# MinipHV2_1.net
KiCad netlist of a schematic drawn in EAGLE
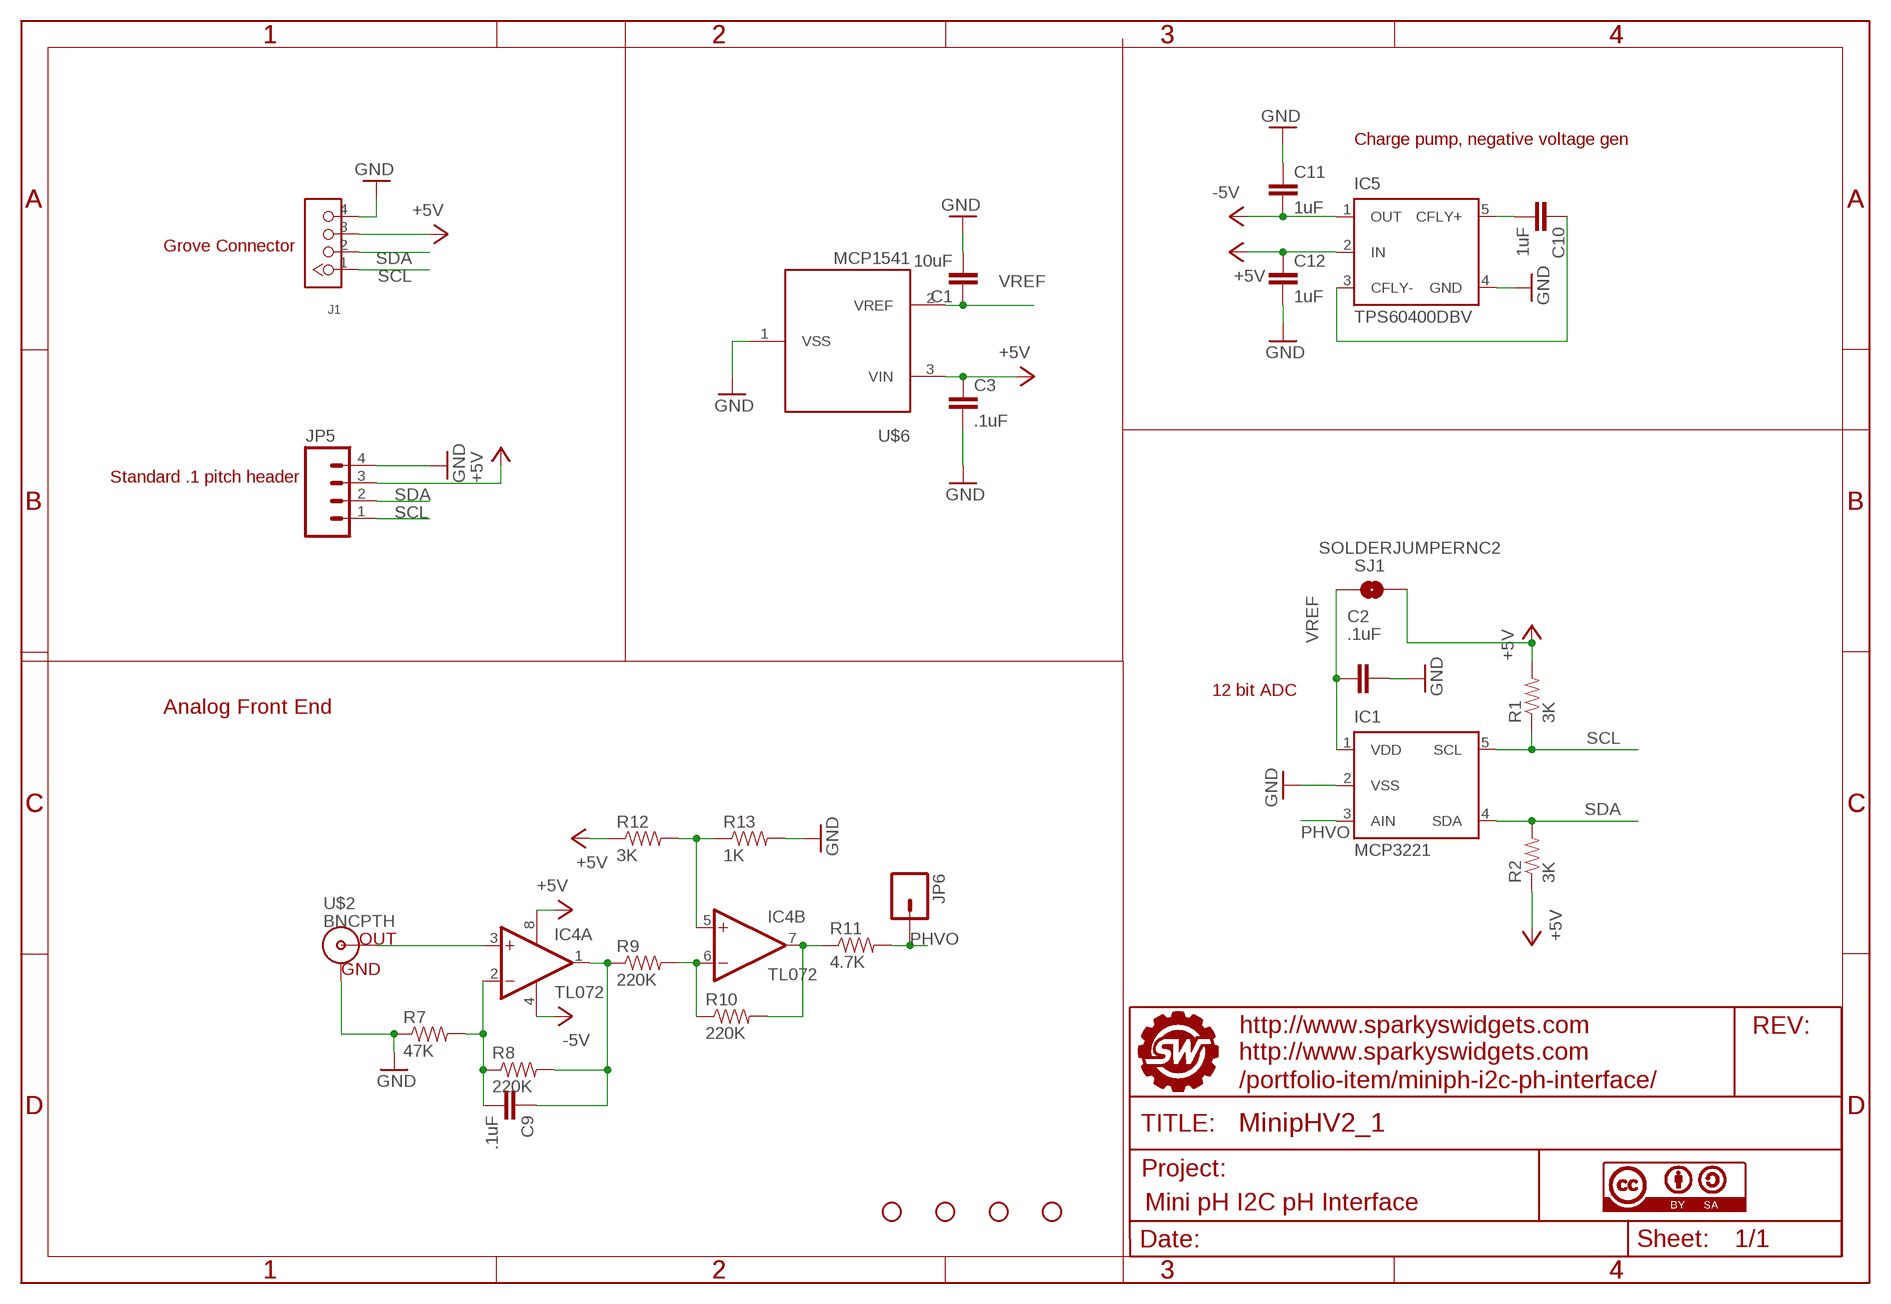
[diagram p0: schematic, sheet 1]

(export (version "E")
  (design (tool "Eeschema 10.0.6"))
  (components
    (comp (ref "C1")
      (value "10uF")
      (footprint "eagle-import:0805")
      (libsource (lib "eagle-import") (part "CAP0805"))
    )
    (comp (ref "C2")
      (value ".1uF")
      (footprint "eagle-import:0805")
      (libsource (lib "eagle-import") (part "CAP0805"))
    )
    (comp (ref "C3")
      (value ".1uF")
      (footprint "eagle-import:0805")
      (libsource (lib "eagle-import") (part "CAP0805"))
    )
    (comp (ref "C9")
      (value ".1uF")
      (footprint "eagle-import:0805")
      (libsource (lib "eagle-import") (part "CAP0805"))
    )
    (comp (ref "C10")
      (value "1uF")
      (footprint "eagle-import:0805")
      (libsource (lib "eagle-import") (part "CAP0805"))
    )
    (comp (ref "C11")
      (value "1uF")
      (footprint "eagle-import:0805")
      (libsource (lib "eagle-import") (part "CAP0805"))
    )
    (comp (ref "C12")
      (value "1uF")
      (footprint "eagle-import:0805")
      (libsource (lib "eagle-import") (part "CAP0805"))
    )
    (comp (ref "IC1")
      (value "MCP3221")
      (footprint "eagle-import:SOT23-DBV")
      (libsource (lib "eagle-import") (part "MCP3221"))
    )
    (comp (ref "IC4")
      (value "TL072")
      (footprint "eagle-import:SO08")
      (libsource (lib "eagle-import") (part "LM358D"))
    )
    (comp (ref "IC5")
      (value "TPS60400DBV")
      (footprint "eagle-import:SOT23-DBV")
      (libsource (lib "eagle-import") (part "TPS60400DBV"))
    )
    (comp (ref "J1")
      (value "TWIG-4P-2.0-2.0")
      (footprint "eagle-import:4P-2.0")
      (libsource (lib "eagle-import") (part "TWIG-4P-2.0-2.0"))
    )
    (comp (ref "JP1")
      (value "STAND-OFF")
      (footprint "eagle-import:STAND-OFF")
      (libsource (lib "eagle-import") (part "STAND-OFF"))
    )
    (comp (ref "JP2")
      (value "STAND-OFF")
      (footprint "eagle-import:STAND-OFF")
      (libsource (lib "eagle-import") (part "STAND-OFF"))
    )
    (comp (ref "JP3")
      (value "STAND-OFF")
      (footprint "eagle-import:STAND-OFF")
      (libsource (lib "eagle-import") (part "STAND-OFF"))
    )
    (comp (ref "JP4")
      (value "STAND-OFF")
      (footprint "eagle-import:STAND-OFF")
      (libsource (lib "eagle-import") (part "STAND-OFF"))
    )
    (comp (ref "JP5")
      (value "M04PTH")
      (footprint "eagle-import:1X04")
      (libsource (lib "eagle-import") (part "M04PTH"))
    )
    (comp (ref "JP6")
      (value "M01PTH_LONGPAD")
      (footprint "eagle-import:1X01_LONGPAD")
      (libsource (lib "eagle-import") (part "M01PTH_LONGPAD"))
    )
    (comp (ref "R1")
      (value "3K")
      (footprint "eagle-import:0805")
      (libsource (lib "eagle-import") (part "RESISTOR0805-RES"))
    )
    (comp (ref "R2")
      (value "3K")
      (footprint "eagle-import:0805")
      (libsource (lib "eagle-import") (part "RESISTOR0805-RES"))
    )
    (comp (ref "R7")
      (value "47K")
      (footprint "eagle-import:0805")
      (libsource (lib "eagle-import") (part "RESISTOR0805-RES"))
    )
    (comp (ref "R8")
      (value "220K")
      (footprint "eagle-import:0805")
      (libsource (lib "eagle-import") (part "RESISTOR0805-RES"))
    )
    (comp (ref "R9")
      (value "220K")
      (footprint "eagle-import:0805")
      (libsource (lib "eagle-import") (part "RESISTOR0805-RES"))
    )
    (comp (ref "R10")
      (value "220K")
      (footprint "eagle-import:0805")
      (libsource (lib "eagle-import") (part "RESISTOR0805-RES"))
    )
    (comp (ref "R11")
      (value "4.7K")
      (footprint "eagle-import:0805")
      (libsource (lib "eagle-import") (part "RESISTOR0805-RES"))
    )
    (comp (ref "R12")
      (value "3K")
      (footprint "eagle-import:0805")
      (libsource (lib "eagle-import") (part "RESISTOR0805-RES"))
    )
    (comp (ref "R13")
      (value "1K")
      (footprint "eagle-import:0805")
      (libsource (lib "eagle-import") (part "RESISTOR0805-RES"))
    )
    (comp (ref "SJ1")
      (value "SOLDERJUMPERNC2")
      (footprint "eagle-import:SJ_2S-NOTRACE")
      (libsource (lib "eagle-import") (part "SOLDERJUMPERNC2"))
    )
    (comp (ref "U$2")
      (value "BNCPTH")
      (footprint "eagle-import:BNC")
      (libsource (lib "eagle-import") (part "BNCPTH"))
    )
    (comp (ref "U$4")
      (value "FRAME_MINIPH")
      (footprint "eagle-import:SWPCBLOGOWITHINFO")
      (fields
        (field (name "PROJECT") "Mini pH I2C pH Interface")
        (field (name "URL1") "/portfolio-item/miniph-i2c-ph-interface/")
      )
      (libsource (lib "eagle-import") (part "FRAME_MINIPH"))
    )
    (comp (ref "U$5")
      (value "CC-BY-SA")
      (footprint "eagle-import:CC-BY-SA")
      (libsource (lib "eagle-import") (part "CC-BY-SA"))
    )
    (comp (ref "U$6")
      (value "MCP1541")
      (footprint "eagle-import:SOT-23")
      (libsource (lib "eagle-import") (part "MCP1541"))
    )
  )
  (nets
    (net (code "1") (name "+5V") (class "Default")
      (node (ref "C12") (pin "1") (pinfunction "1_1") (pintype "passive"))
      (node (ref "C3") (pin "1") (pinfunction "1_1") (pintype "passive"))
      (node (ref "IC4") (pin "8") (pinfunction "V+_8") (pintype "power_in"))
      (node (ref "IC5") (pin "2") (pinfunction "IN_2") (pintype "input"))
      (node (ref "J1") (pin "3") (pinfunction "3_3") (pintype "bidirectional"))
      (node (ref "JP5") (pin "3") (pinfunction "3_3") (pintype "passive"))
      (node (ref "R1") (pin "2") (pinfunction "2_2") (pintype "passive"))
      (node (ref "R12") (pin "1") (pinfunction "1_1") (pintype "passive"))
      (node (ref "R2") (pin "1") (pinfunction "1_1") (pintype "passive"))
      (node (ref "SJ1") (pin "2") (pinfunction "2_2") (pintype "passive"))
      (node (ref "U$6") (pin "3") (pinfunction "VIN_3") (pintype "power_in"))
    )
    (net (code "2") (name "-5V") (class "Default")
      (node (ref "C11") (pin "2") (pinfunction "2_2") (pintype "passive"))
      (node (ref "IC4") (pin "4") (pinfunction "V-_4") (pintype "power_in"))
      (node (ref "IC5") (pin "1") (pinfunction "OUT_1") (pintype "input"))
    )
    (net (code "3") (name "/PHVO") (class "Default")
      (node (ref "IC1") (pin "3") (pinfunction "AIN_3") (pintype "input"))
      (node (ref "JP6") (pin "1") (pinfunction "1_1") (pintype "passive"))
      (node (ref "R11") (pin "2") (pinfunction "2_2") (pintype "passive"))
    )
    (net (code "4") (name "/SCL") (class "Default")
      (node (ref "IC1") (pin "5") (pinfunction "SCL_5") (pintype "bidirectional"))
      (node (ref "J1") (pin "1") (pinfunction "1_1") (pintype "bidirectional"))
      (node (ref "JP5") (pin "1") (pinfunction "1_1") (pintype "passive"))
      (node (ref "R1") (pin "1") (pinfunction "1_1") (pintype "passive"))
    )
    (net (code "5") (name "/SDA") (class "Default")
      (node (ref "IC1") (pin "4") (pinfunction "SDA_4") (pintype "bidirectional"))
      (node (ref "J1") (pin "2") (pinfunction "2_2") (pintype "bidirectional"))
      (node (ref "JP5") (pin "2") (pinfunction "2_2") (pintype "passive"))
      (node (ref "R2") (pin "2") (pinfunction "2_2") (pintype "passive"))
    )
    (net (code "6") (name "/VREF") (class "Default")
      (node (ref "C1") (pin "1") (pinfunction "1_1") (pintype "passive"))
      (node (ref "C2") (pin "2") (pinfunction "2_2") (pintype "passive"))
      (node (ref "IC1") (pin "1") (pinfunction "VDD_1") (pintype "power_in"))
      (node (ref "SJ1") (pin "1") (pinfunction "1_1") (pintype "passive"))
      (node (ref "U$6") (pin "2") (pinfunction "VREF_2") (pintype "output"))
    )
    (net (code "7") (name "GND") (class "Default")
      (node (ref "C1") (pin "2") (pinfunction "2_2") (pintype "passive"))
      (node (ref "C11") (pin "1") (pinfunction "1_1") (pintype "passive"))
      (node (ref "C12") (pin "2") (pinfunction "2_2") (pintype "passive"))
      (node (ref "C2") (pin "1") (pinfunction "1_1") (pintype "passive"))
      (node (ref "C3") (pin "2") (pinfunction "2_2") (pintype "passive"))
      (node (ref "IC1") (pin "2") (pinfunction "VSS_2") (pintype "power_in"))
      (node (ref "IC5") (pin "4") (pinfunction "GND_4") (pintype "passive"))
      (node (ref "J1") (pin "4") (pinfunction "4_4") (pintype "bidirectional"))
      (node (ref "JP5") (pin "4") (pinfunction "4_4") (pintype "passive"))
      (node (ref "R13") (pin "2") (pinfunction "2_2") (pintype "passive"))
      (node (ref "R7") (pin "1") (pinfunction "1_1") (pintype "passive"))
      (node (ref "U$2") (pin "GND") (pinfunction "GND_GND") (pintype "bidirectional"))
      (node (ref "U$6") (pin "1") (pinfunction "VSS_1") (pintype "power_in"))
    )
    (net (code "8") (name "Net-(IC4A-+IN)") (class "Default")
      (node (ref "IC4") (pin "3") (pinfunction "+IN_3") (pintype "input"))
      (node (ref "U$2") (pin "S") (pinfunction "OUT_S") (pintype "bidirectional"))
    )
    (net (code "9") (name "Net-(IC4A--IN)") (class "Default")
      (node (ref "C9") (pin "2") (pinfunction "2_2") (pintype "passive"))
      (node (ref "IC4") (pin "2") (pinfunction "-IN_2") (pintype "input"))
      (node (ref "R7") (pin "2") (pinfunction "2_2") (pintype "passive"))
      (node (ref "R8") (pin "1") (pinfunction "1_1") (pintype "passive"))
    )
    (net (code "10") (name "Net-(IC4A-OUT)") (class "Default")
      (node (ref "C9") (pin "1") (pinfunction "1_1") (pintype "passive"))
      (node (ref "IC4") (pin "1") (pinfunction "OUT_1") (pintype "output"))
      (node (ref "R8") (pin "2") (pinfunction "2_2") (pintype "passive"))
      (node (ref "R9") (pin "1") (pinfunction "1_1") (pintype "passive"))
    )
    (net (code "11") (name "Net-(IC4B-+IN)") (class "Default")
      (node (ref "IC4") (pin "5") (pinfunction "+IN_5") (pintype "input"))
      (node (ref "R12") (pin "2") (pinfunction "2_2") (pintype "passive"))
      (node (ref "R13") (pin "1") (pinfunction "1_1") (pintype "passive"))
    )
    (net (code "12") (name "Net-(IC4B--IN)") (class "Default")
      (node (ref "IC4") (pin "6") (pinfunction "-IN_6") (pintype "input"))
      (node (ref "R10") (pin "1") (pinfunction "1_1") (pintype "passive"))
      (node (ref "R9") (pin "2") (pinfunction "2_2") (pintype "passive"))
    )
    (net (code "13") (name "Net-(IC4B-OUT)") (class "Default")
      (node (ref "IC4") (pin "7") (pinfunction "OUT_7") (pintype "output"))
      (node (ref "R10") (pin "2") (pinfunction "2_2") (pintype "passive"))
      (node (ref "R11") (pin "1") (pinfunction "1_1") (pintype "passive"))
    )
    (net (code "14") (name "Net-(IC5-CFLY+)") (class "Default")
      (node (ref "C10") (pin "2") (pinfunction "2_2") (pintype "passive"))
      (node (ref "IC5") (pin "5") (pinfunction "CFLY+_5") (pintype "passive"))
    )
    (net (code "15") (name "Net-(IC5-CFLY-)") (class "Default")
      (node (ref "C10") (pin "1") (pinfunction "1_1") (pintype "passive"))
      (node (ref "IC5") (pin "3") (pinfunction "CFLY-_3") (pintype "power_in"))
    )
  )
)
